# h-bridge_0_8.net
KiCad netlist of a schematic drawn in EAGLE
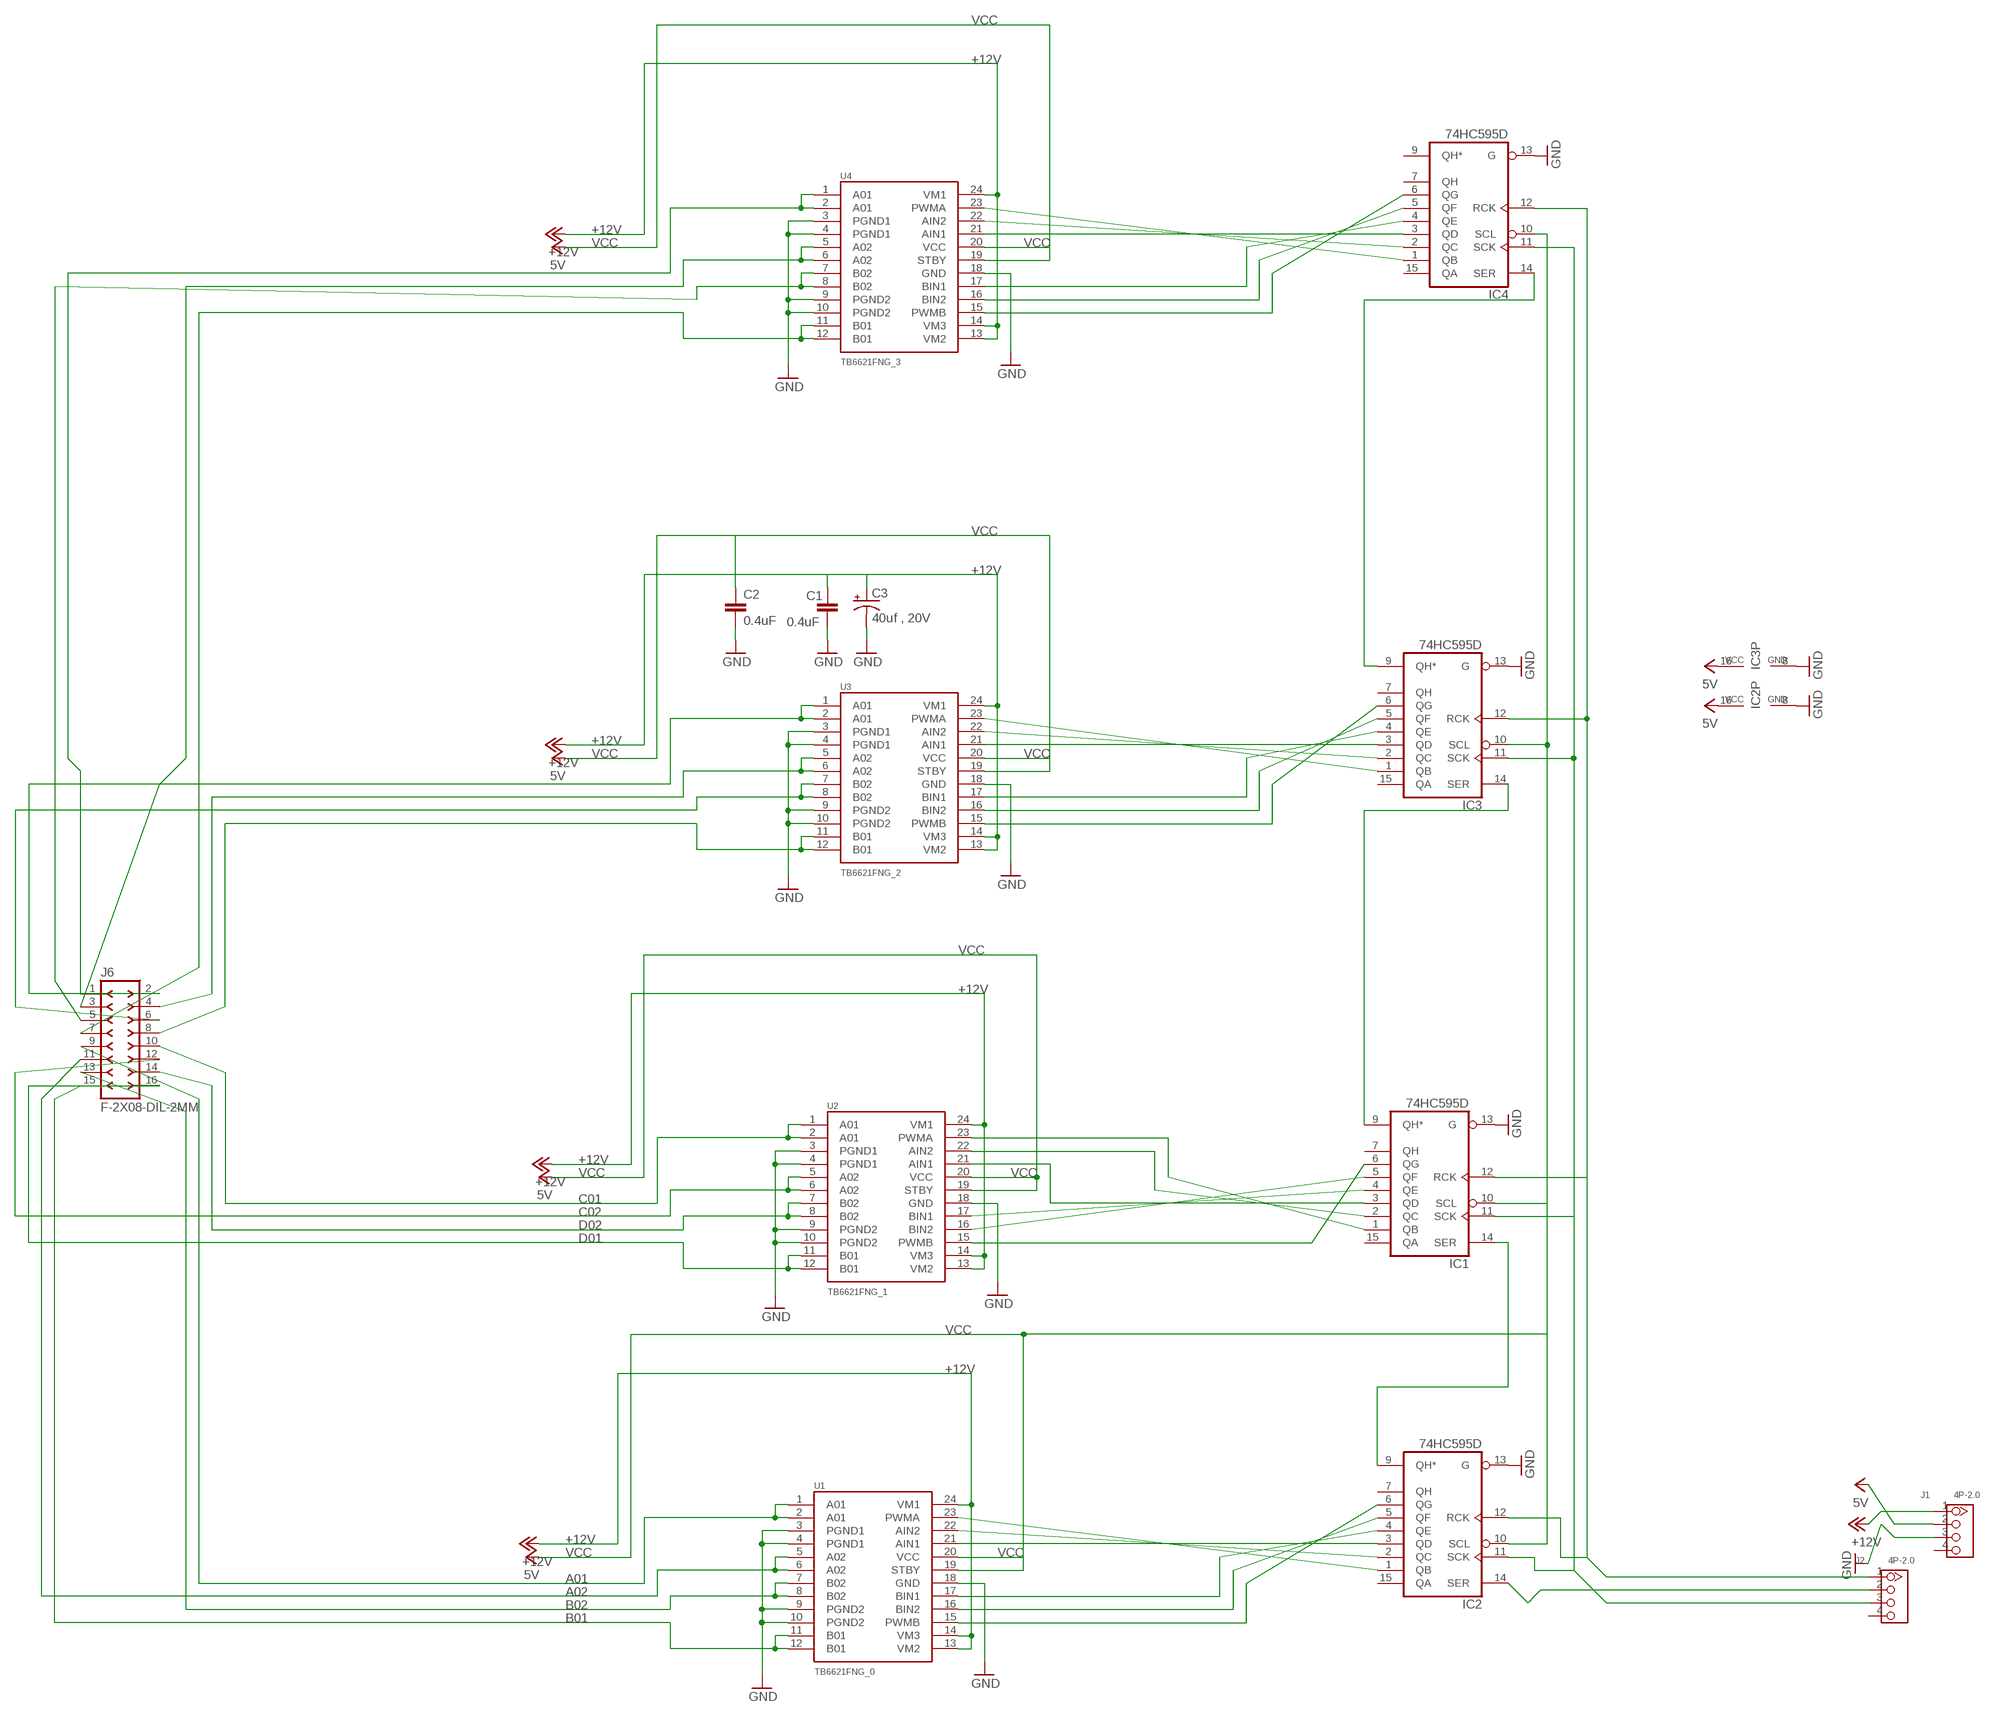
[diagram p0: schematic, sheet 1]

(export (version "E")
  (design (tool "Eeschema 10.0.6"))
  (components
    (comp (ref "C1")
      (value "0.4uF")
      (footprint "eagle-import:0402-CAP")
      (libsource (lib "eagle-import") (part "CAP0402-CAP"))
    )
    (comp (ref "C2")
      (value "0.4uF")
      (footprint "eagle-import:0402-CAP")
      (libsource (lib "eagle-import") (part "CAP0402-CAP"))
    )
    (comp (ref "C3")
      (value "40uf , 20V")
      (footprint "eagle-import:EIA3528")
      (libsource (lib "eagle-import") (part "CAP_POL3528"))
    )
    (comp (ref "IC1")
      (value "74HC595D")
      (footprint "eagle-import:SO16")
      (libsource (lib "eagle-import") (part "74595DHC"))
    )
    (comp (ref "IC2")
      (value "74HC595D")
      (footprint "eagle-import:SO16")
      (libsource (lib "eagle-import") (part "74595DHC"))
    )
    (comp (ref "IC3")
      (value "74HC595D")
      (footprint "eagle-import:SO16")
      (libsource (lib "eagle-import") (part "74595DHC"))
    )
    (comp (ref "IC4")
      (value "74HC595D")
      (footprint "eagle-import:SO16")
      (libsource (lib "eagle-import") (part "74595DHC"))
    )
    (comp (ref "J1")
      (value "4P-2.0")
      (footprint "eagle-import:HW4-2.0")
      (libsource (lib "eagle-import") (part "GROVE-CONNECTOR-DIP(4P-2.0)"))
    )
    (comp (ref "J2")
      (value "4P-2.0")
      (footprint "eagle-import:HW4-2.0")
      (libsource (lib "eagle-import") (part "GROVE-CONNECTOR-DIP(4P-2.0)"))
    )
    (comp (ref "J6")
      (value "F-2X08-DIL-2MM")
      (footprint "eagle-import:DIL-2MM-2X08")
      (libsource (lib "eagle-import") (part "F-2X08-DIL-2MM"))
    )
    (comp (ref "U1")
      (value "TB6621FNG_0")
      (footprint "eagle-import:SSOP24")
      (libsource (lib "eagle-import") (part "TB6621FNG"))
    )
    (comp (ref "U2")
      (value "TB6621FNG_1")
      (footprint "eagle-import:SSOP24")
      (libsource (lib "eagle-import") (part "TB6621FNG"))
    )
    (comp (ref "U3")
      (value "TB6621FNG_2")
      (footprint "eagle-import:SSOP24")
      (libsource (lib "eagle-import") (part "TB6621FNG"))
    )
    (comp (ref "U4")
      (value "TB6621FNG_3")
      (footprint "eagle-import:SSOP24")
      (libsource (lib "eagle-import") (part "TB6621FNG"))
    )
  )
  (nets
    (net (code "1") (name "+12V") (class "Default")
      (node (ref "C1") (pin "1") (pinfunction "1_1") (pintype "passive"))
      (node (ref "C3") (pin "A") (pinfunction "+_A") (pintype "passive"))
      (node (ref "J1") (pin "1") (pinfunction "1_1") (pintype "bidirectional"))
      (node (ref "U1") (pin "13") (pinfunction "VM2_13") (pintype "bidirectional"))
      (node (ref "U1") (pin "14") (pinfunction "VM3_14") (pintype "bidirectional"))
      (node (ref "U1") (pin "24") (pinfunction "VM1_24") (pintype "bidirectional"))
      (node (ref "U2") (pin "13") (pinfunction "VM2_13") (pintype "bidirectional"))
      (node (ref "U2") (pin "14") (pinfunction "VM3_14") (pintype "bidirectional"))
      (node (ref "U2") (pin "24") (pinfunction "VM1_24") (pintype "bidirectional"))
      (node (ref "U3") (pin "13") (pinfunction "VM2_13") (pintype "bidirectional"))
      (node (ref "U3") (pin "14") (pinfunction "VM3_14") (pintype "bidirectional"))
      (node (ref "U3") (pin "24") (pinfunction "VM1_24") (pintype "bidirectional"))
      (node (ref "U4") (pin "13") (pinfunction "VM2_13") (pintype "bidirectional"))
      (node (ref "U4") (pin "14") (pinfunction "VM3_14") (pintype "bidirectional"))
      (node (ref "U4") (pin "24") (pinfunction "VM1_24") (pintype "bidirectional"))
    )
    (net (code "2") (name "A01") (class "Default")
      (node (ref "J6") (pin "9") (pinfunction "9_9") (pintype "passive"))
      (node (ref "U1") (pin "1") (pinfunction "A01_1") (pintype "bidirectional"))
      (node (ref "U1") (pin "2") (pinfunction "A01_2") (pintype "bidirectional"))
    )
    (net (code "3") (name "A02") (class "Default")
      (node (ref "J6") (pin "11") (pinfunction "11_11") (pintype "passive"))
      (node (ref "U1") (pin "5") (pinfunction "A02_5") (pintype "bidirectional"))
      (node (ref "U1") (pin "6") (pinfunction "A02_6") (pintype "bidirectional"))
    )
    (net (code "4") (name "B01") (class "Default")
      (node (ref "J6") (pin "15") (pinfunction "15_15") (pintype "passive"))
      (node (ref "U1") (pin "11") (pinfunction "B01_11") (pintype "bidirectional"))
      (node (ref "U1") (pin "12") (pinfunction "B01_12") (pintype "bidirectional"))
    )
    (net (code "5") (name "B02") (class "Default")
      (node (ref "J6") (pin "13") (pinfunction "13_13") (pintype "passive"))
      (node (ref "U1") (pin "7") (pinfunction "B02_7") (pintype "bidirectional"))
      (node (ref "U1") (pin "8") (pinfunction "B02_8") (pintype "bidirectional"))
    )
    (net (code "6") (name "C01") (class "Default")
      (node (ref "J6") (pin "10") (pinfunction "10_10") (pintype "passive"))
      (node (ref "U2") (pin "1") (pinfunction "A01_1") (pintype "bidirectional"))
      (node (ref "U2") (pin "2") (pinfunction "A01_2") (pintype "bidirectional"))
    )
    (net (code "7") (name "C02") (class "Default")
      (node (ref "J6") (pin "12") (pinfunction "12_12") (pintype "passive"))
      (node (ref "U2") (pin "5") (pinfunction "A02_5") (pintype "bidirectional"))
      (node (ref "U2") (pin "6") (pinfunction "A02_6") (pintype "bidirectional"))
    )
    (net (code "8") (name "D01") (class "Default")
      (node (ref "J6") (pin "16") (pinfunction "16_16") (pintype "passive"))
      (node (ref "U2") (pin "11") (pinfunction "B01_11") (pintype "bidirectional"))
      (node (ref "U2") (pin "12") (pinfunction "B01_12") (pintype "bidirectional"))
    )
    (net (code "9") (name "D02") (class "Default")
      (node (ref "J6") (pin "14") (pinfunction "14_14") (pintype "passive"))
      (node (ref "U2") (pin "7") (pinfunction "B02_7") (pintype "bidirectional"))
      (node (ref "U2") (pin "8") (pinfunction "B02_8") (pintype "bidirectional"))
    )
    (net (code "10") (name "GND") (class "Default")
      (node (ref "C1") (pin "2") (pinfunction "2_2") (pintype "passive"))
      (node (ref "C2") (pin "2") (pinfunction "2_2") (pintype "passive"))
      (node (ref "C3") (pin "C") (pinfunction "-_C") (pintype "passive"))
      (node (ref "IC1") (pin "13") (pinfunction "G_13") (pintype "input"))
      (node (ref "IC2") (pin "13") (pinfunction "G_13") (pintype "input"))
      (node (ref "IC2") (pin "8") (pinfunction "GND_8") (pintype "power_in"))
      (node (ref "IC3") (pin "13") (pinfunction "G_13") (pintype "input"))
      (node (ref "IC3") (pin "8") (pinfunction "GND_8") (pintype "power_in"))
      (node (ref "IC4") (pin "13") (pinfunction "G_13") (pintype "input"))
      (node (ref "J1") (pin "3") (pinfunction "3_3") (pintype "bidirectional"))
      (node (ref "U1") (pin "10") (pinfunction "PGND2_10") (pintype "bidirectional"))
      (node (ref "U1") (pin "18") (pinfunction "GND_18") (pintype "bidirectional"))
      (node (ref "U1") (pin "3") (pinfunction "PGND1_3") (pintype "bidirectional"))
      (node (ref "U1") (pin "4") (pinfunction "PGND1_4") (pintype "bidirectional"))
      (node (ref "U1") (pin "9") (pinfunction "PGND2_9") (pintype "bidirectional"))
      (node (ref "U2") (pin "10") (pinfunction "PGND2_10") (pintype "bidirectional"))
      (node (ref "U2") (pin "18") (pinfunction "GND_18") (pintype "bidirectional"))
      (node (ref "U2") (pin "3") (pinfunction "PGND1_3") (pintype "bidirectional"))
      (node (ref "U2") (pin "4") (pinfunction "PGND1_4") (pintype "bidirectional"))
      (node (ref "U2") (pin "9") (pinfunction "PGND2_9") (pintype "bidirectional"))
      (node (ref "U3") (pin "10") (pinfunction "PGND2_10") (pintype "bidirectional"))
      (node (ref "U3") (pin "18") (pinfunction "GND_18") (pintype "bidirectional"))
      (node (ref "U3") (pin "3") (pinfunction "PGND1_3") (pintype "bidirectional"))
      (node (ref "U3") (pin "4") (pinfunction "PGND1_4") (pintype "bidirectional"))
      (node (ref "U3") (pin "9") (pinfunction "PGND2_9") (pintype "bidirectional"))
      (node (ref "U4") (pin "10") (pinfunction "PGND2_10") (pintype "bidirectional"))
      (node (ref "U4") (pin "18") (pinfunction "GND_18") (pintype "bidirectional"))
      (node (ref "U4") (pin "3") (pinfunction "PGND1_3") (pintype "bidirectional"))
      (node (ref "U4") (pin "4") (pinfunction "PGND1_4") (pintype "bidirectional"))
      (node (ref "U4") (pin "9") (pinfunction "PGND2_9") (pintype "bidirectional"))
    )
    (net (code "11") (name "Net-(IC1A-QB)") (class "Default")
      (node (ref "IC1") (pin "1") (pinfunction "QB_1") (pintype "tri_state"))
      (node (ref "U2") (pin "23") (pinfunction "PWMA_23") (pintype "bidirectional"))
    )
    (net (code "12") (name "Net-(IC1A-QC)") (class "Default")
      (node (ref "IC1") (pin "2") (pinfunction "QC_2") (pintype "tri_state"))
      (node (ref "U2") (pin "22") (pinfunction "AIN2_22") (pintype "bidirectional"))
    )
    (net (code "13") (name "Net-(IC1A-QD)") (class "Default")
      (node (ref "IC1") (pin "3") (pinfunction "QD_3") (pintype "tri_state"))
      (node (ref "U2") (pin "21") (pinfunction "AIN1_21") (pintype "bidirectional"))
    )
    (net (code "14") (name "Net-(IC1A-QE)") (class "Default")
      (node (ref "IC1") (pin "4") (pinfunction "QE_4") (pintype "tri_state"))
      (node (ref "U2") (pin "17") (pinfunction "BIN1_17") (pintype "bidirectional"))
    )
    (net (code "15") (name "Net-(IC1A-QF)") (class "Default")
      (node (ref "IC1") (pin "5") (pinfunction "QF_5") (pintype "tri_state"))
      (node (ref "U2") (pin "16") (pinfunction "BIN2_16") (pintype "bidirectional"))
    )
    (net (code "16") (name "Net-(IC1A-QG)") (class "Default")
      (node (ref "IC1") (pin "6") (pinfunction "QG_6") (pintype "tri_state"))
      (node (ref "U2") (pin "15") (pinfunction "PWMB_15") (pintype "bidirectional"))
    )
    (net (code "17") (name "Net-(IC1A-QH*)") (class "Default")
      (node (ref "IC1") (pin "9") (pinfunction "QH*_9") (pintype "tri_state"))
      (node (ref "IC3") (pin "14") (pinfunction "SER_14") (pintype "input"))
    )
    (net (code "18") (name "Net-(IC1A-RCK)") (class "Default")
      (node (ref "IC1") (pin "12") (pinfunction "RCK_12") (pintype "input"))
      (node (ref "IC2") (pin "12") (pinfunction "RCK_12") (pintype "input"))
      (node (ref "IC3") (pin "12") (pinfunction "RCK_12") (pintype "input"))
      (node (ref "IC4") (pin "12") (pinfunction "RCK_12") (pintype "input"))
      (node (ref "J2") (pin "1") (pinfunction "1_1") (pintype "bidirectional"))
    )
    (net (code "19") (name "Net-(IC1A-SCK)") (class "Default")
      (node (ref "IC1") (pin "11") (pinfunction "SCK_11") (pintype "input"))
      (node (ref "IC2") (pin "11") (pinfunction "SCK_11") (pintype "input"))
      (node (ref "IC3") (pin "11") (pinfunction "SCK_11") (pintype "input"))
      (node (ref "IC4") (pin "11") (pinfunction "SCK_11") (pintype "input"))
    )
    (net (code "20") (name "Net-(IC1A-SER)") (class "Default")
      (node (ref "IC1") (pin "14") (pinfunction "SER_14") (pintype "input"))
      (node (ref "IC2") (pin "9") (pinfunction "QH*_9") (pintype "tri_state"))
    )
    (net (code "21") (name "Net-(IC2A-QB)") (class "Default")
      (node (ref "IC2") (pin "1") (pinfunction "QB_1") (pintype "tri_state"))
      (node (ref "U1") (pin "23") (pinfunction "PWMA_23") (pintype "bidirectional"))
    )
    (net (code "22") (name "Net-(IC2A-QC)") (class "Default")
      (node (ref "IC2") (pin "2") (pinfunction "QC_2") (pintype "tri_state"))
      (node (ref "U1") (pin "22") (pinfunction "AIN2_22") (pintype "bidirectional"))
    )
    (net (code "23") (name "Net-(IC2A-QD)") (class "Default")
      (node (ref "IC2") (pin "3") (pinfunction "QD_3") (pintype "tri_state"))
      (node (ref "U1") (pin "21") (pinfunction "AIN1_21") (pintype "bidirectional"))
    )
    (net (code "24") (name "Net-(IC2A-QE)") (class "Default")
      (node (ref "IC2") (pin "4") (pinfunction "QE_4") (pintype "tri_state"))
      (node (ref "U1") (pin "17") (pinfunction "BIN1_17") (pintype "bidirectional"))
    )
    (net (code "25") (name "Net-(IC2A-QF)") (class "Default")
      (node (ref "IC2") (pin "5") (pinfunction "QF_5") (pintype "tri_state"))
      (node (ref "U1") (pin "16") (pinfunction "BIN2_16") (pintype "bidirectional"))
    )
    (net (code "26") (name "Net-(IC2A-QG)") (class "Default")
      (node (ref "IC2") (pin "6") (pinfunction "QG_6") (pintype "tri_state"))
      (node (ref "U1") (pin "15") (pinfunction "PWMB_15") (pintype "bidirectional"))
    )
    (net (code "27") (name "Net-(IC2A-SER)") (class "Default")
      (node (ref "IC2") (pin "14") (pinfunction "SER_14") (pintype "input"))
      (node (ref "J2") (pin "2") (pinfunction "2_2") (pintype "bidirectional"))
    )
    (net (code "28") (name "Net-(IC3A-QB)") (class "Default")
      (node (ref "IC3") (pin "1") (pinfunction "QB_1") (pintype "tri_state"))
      (node (ref "U3") (pin "23") (pinfunction "PWMA_23") (pintype "bidirectional"))
    )
    (net (code "29") (name "Net-(IC3A-QC)") (class "Default")
      (node (ref "IC3") (pin "2") (pinfunction "QC_2") (pintype "tri_state"))
      (node (ref "U3") (pin "22") (pinfunction "AIN2_22") (pintype "bidirectional"))
    )
    (net (code "30") (name "Net-(IC3A-QD)") (class "Default")
      (node (ref "IC3") (pin "3") (pinfunction "QD_3") (pintype "tri_state"))
      (node (ref "U3") (pin "21") (pinfunction "AIN1_21") (pintype "bidirectional"))
    )
    (net (code "31") (name "Net-(IC3A-QE)") (class "Default")
      (node (ref "IC3") (pin "4") (pinfunction "QE_4") (pintype "tri_state"))
      (node (ref "U3") (pin "17") (pinfunction "BIN1_17") (pintype "bidirectional"))
    )
    (net (code "32") (name "Net-(IC3A-QF)") (class "Default")
      (node (ref "IC3") (pin "5") (pinfunction "QF_5") (pintype "tri_state"))
      (node (ref "U3") (pin "16") (pinfunction "BIN2_16") (pintype "bidirectional"))
    )
    (net (code "33") (name "Net-(IC3A-QG)") (class "Default")
      (node (ref "IC3") (pin "6") (pinfunction "QG_6") (pintype "tri_state"))
      (node (ref "U3") (pin "15") (pinfunction "PWMB_15") (pintype "bidirectional"))
    )
    (net (code "34") (name "Net-(IC3A-QH*)") (class "Default")
      (node (ref "IC3") (pin "9") (pinfunction "QH*_9") (pintype "tri_state"))
      (node (ref "IC4") (pin "14") (pinfunction "SER_14") (pintype "input"))
    )
    (net (code "35") (name "Net-(IC4A-QB)") (class "Default")
      (node (ref "IC4") (pin "1") (pinfunction "QB_1") (pintype "tri_state"))
      (node (ref "U4") (pin "23") (pinfunction "PWMA_23") (pintype "bidirectional"))
    )
    (net (code "36") (name "Net-(IC4A-QC)") (class "Default")
      (node (ref "IC4") (pin "2") (pinfunction "QC_2") (pintype "tri_state"))
      (node (ref "U4") (pin "22") (pinfunction "AIN2_22") (pintype "bidirectional"))
    )
    (net (code "37") (name "Net-(IC4A-QD)") (class "Default")
      (node (ref "IC4") (pin "3") (pinfunction "QD_3") (pintype "tri_state"))
      (node (ref "U4") (pin "21") (pinfunction "AIN1_21") (pintype "bidirectional"))
    )
    (net (code "38") (name "Net-(IC4A-QE)") (class "Default")
      (node (ref "IC4") (pin "4") (pinfunction "QE_4") (pintype "tri_state"))
      (node (ref "U4") (pin "17") (pinfunction "BIN1_17") (pintype "bidirectional"))
    )
    (net (code "39") (name "Net-(IC4A-QF)") (class "Default")
      (node (ref "IC4") (pin "5") (pinfunction "QF_5") (pintype "tri_state"))
      (node (ref "U4") (pin "16") (pinfunction "BIN2_16") (pintype "bidirectional"))
    )
    (net (code "40") (name "Net-(IC4A-QG)") (class "Default")
      (node (ref "IC4") (pin "6") (pinfunction "QG_6") (pintype "tri_state"))
      (node (ref "U4") (pin "15") (pinfunction "PWMB_15") (pintype "bidirectional"))
    )
    (net (code "41") (name "Net-(J6-Pad1)") (class "Default")
      (node (ref "J6") (pin "1") (pinfunction "1_1") (pintype "passive"))
      (node (ref "U4") (pin "1") (pinfunction "A01_1") (pintype "bidirectional"))
      (node (ref "U4") (pin "2") (pinfunction "A01_2") (pintype "bidirectional"))
    )
    (net (code "42") (name "Net-(J6-Pad2)") (class "Default")
      (node (ref "J6") (pin "2") (pinfunction "2_2") (pintype "passive"))
      (node (ref "U3") (pin "1") (pinfunction "A01_1") (pintype "bidirectional"))
      (node (ref "U3") (pin "2") (pinfunction "A01_2") (pintype "bidirectional"))
    )
    (net (code "43") (name "Net-(J6-Pad3)") (class "Default")
      (node (ref "J6") (pin "3") (pinfunction "3_3") (pintype "passive"))
      (node (ref "U4") (pin "5") (pinfunction "A02_5") (pintype "bidirectional"))
      (node (ref "U4") (pin "6") (pinfunction "A02_6") (pintype "bidirectional"))
    )
    (net (code "44") (name "Net-(J6-Pad4)") (class "Default")
      (node (ref "J6") (pin "4") (pinfunction "4_4") (pintype "passive"))
      (node (ref "U3") (pin "5") (pinfunction "A02_5") (pintype "bidirectional"))
      (node (ref "U3") (pin "6") (pinfunction "A02_6") (pintype "bidirectional"))
    )
    (net (code "45") (name "Net-(J6-Pad5)") (class "Default")
      (node (ref "J6") (pin "5") (pinfunction "5_5") (pintype "passive"))
      (node (ref "U4") (pin "7") (pinfunction "B02_7") (pintype "bidirectional"))
      (node (ref "U4") (pin "8") (pinfunction "B02_8") (pintype "bidirectional"))
    )
    (net (code "46") (name "Net-(J6-Pad6)") (class "Default")
      (node (ref "J6") (pin "6") (pinfunction "6_6") (pintype "passive"))
      (node (ref "U3") (pin "7") (pinfunction "B02_7") (pintype "bidirectional"))
      (node (ref "U3") (pin "8") (pinfunction "B02_8") (pintype "bidirectional"))
    )
    (net (code "47") (name "Net-(J6-Pad7)") (class "Default")
      (node (ref "J6") (pin "7") (pinfunction "7_7") (pintype "passive"))
      (node (ref "U4") (pin "11") (pinfunction "B01_11") (pintype "bidirectional"))
      (node (ref "U4") (pin "12") (pinfunction "B01_12") (pintype "bidirectional"))
    )
    (net (code "48") (name "Net-(J6-Pad8)") (class "Default")
      (node (ref "J6") (pin "8") (pinfunction "8_8") (pintype "passive"))
      (node (ref "U3") (pin "11") (pinfunction "B01_11") (pintype "bidirectional"))
      (node (ref "U3") (pin "12") (pinfunction "B01_12") (pintype "bidirectional"))
    )
    (net (code "49") (name "VCC") (class "Default")
      (node (ref "C2") (pin "1") (pinfunction "1_1") (pintype "passive"))
      (node (ref "IC1") (pin "10") (pinfunction "SCL_10") (pintype "input"))
      (node (ref "IC2") (pin "10") (pinfunction "SCL_10") (pintype "input"))
      (node (ref "IC2") (pin "16") (pinfunction "VCC_16") (pintype "power_in"))
      (node (ref "IC3") (pin "10") (pinfunction "SCL_10") (pintype "input"))
      (node (ref "IC3") (pin "16") (pinfunction "VCC_16") (pintype "power_in"))
      (node (ref "IC4") (pin "10") (pinfunction "SCL_10") (pintype "input"))
      (node (ref "J1") (pin "2") (pinfunction "2_2") (pintype "bidirectional"))
      (node (ref "U1") (pin "19") (pinfunction "STBY_19") (pintype "bidirectional"))
      (node (ref "U1") (pin "20") (pinfunction "VCC_20") (pintype "bidirectional"))
      (node (ref "U2") (pin "19") (pinfunction "STBY_19") (pintype "bidirectional"))
      (node (ref "U2") (pin "20") (pinfunction "VCC_20") (pintype "bidirectional"))
      (node (ref "U3") (pin "19") (pinfunction "STBY_19") (pintype "bidirectional"))
      (node (ref "U3") (pin "20") (pinfunction "VCC_20") (pintype "bidirectional"))
      (node (ref "U4") (pin "19") (pinfunction "STBY_19") (pintype "bidirectional"))
      (node (ref "U4") (pin "20") (pinfunction "VCC_20") (pintype "bidirectional"))
    )
    (net (code "50") (name "unconnected-(IC1A-QA-Pad15)") (class "Default")
      (node (ref "IC1") (pin "15") (pinfunction "QA_15") (pintype "tri_state"))
    )
    (net (code "51") (name "unconnected-(IC1A-QH-Pad7)") (class "Default")
      (node (ref "IC1") (pin "7") (pinfunction "QH_7") (pintype "tri_state"))
    )
    (net (code "52") (name "unconnected-(IC2A-QA-Pad15)") (class "Default")
      (node (ref "IC2") (pin "15") (pinfunction "QA_15") (pintype "tri_state"))
    )
    (net (code "53") (name "unconnected-(IC2A-QH-Pad7)") (class "Default")
      (node (ref "IC2") (pin "7") (pinfunction "QH_7") (pintype "tri_state"))
    )
    (net (code "54") (name "unconnected-(IC3A-QA-Pad15)") (class "Default")
      (node (ref "IC3") (pin "15") (pinfunction "QA_15") (pintype "tri_state"))
    )
    (net (code "55") (name "unconnected-(IC3A-QH-Pad7)") (class "Default")
      (node (ref "IC3") (pin "7") (pinfunction "QH_7") (pintype "tri_state"))
    )
    (net (code "56") (name "unconnected-(IC4A-QA-Pad15)") (class "Default")
      (node (ref "IC4") (pin "15") (pinfunction "QA_15") (pintype "tri_state"))
    )
    (net (code "57") (name "unconnected-(IC4A-QH*-Pad9)") (class "Default")
      (node (ref "IC4") (pin "9") (pinfunction "QH*_9") (pintype "tri_state"))
    )
    (net (code "58") (name "unconnected-(IC4A-QH-Pad7)") (class "Default")
      (node (ref "IC4") (pin "7") (pinfunction "QH_7") (pintype "tri_state"))
    )
    (net (code "59") (name "unconnected-(J1-Pad4)") (class "Default")
      (node (ref "J1") (pin "4") (pinfunction "4_4") (pintype "bidirectional"))
    )
    (net (code "60") (name "unconnected-(J2-Pad3)") (class "Default")
      (node (ref "J2") (pin "3") (pinfunction "3_3") (pintype "bidirectional"))
    )
    (net (code "61") (name "unconnected-(J2-Pad4)") (class "Default")
      (node (ref "J2") (pin "4") (pinfunction "4_4") (pintype "bidirectional"))
    )
  )
)
